# pca10040_sheet5_power_supply.net
KiCad netlist of a schematic drawn in Altium Designer
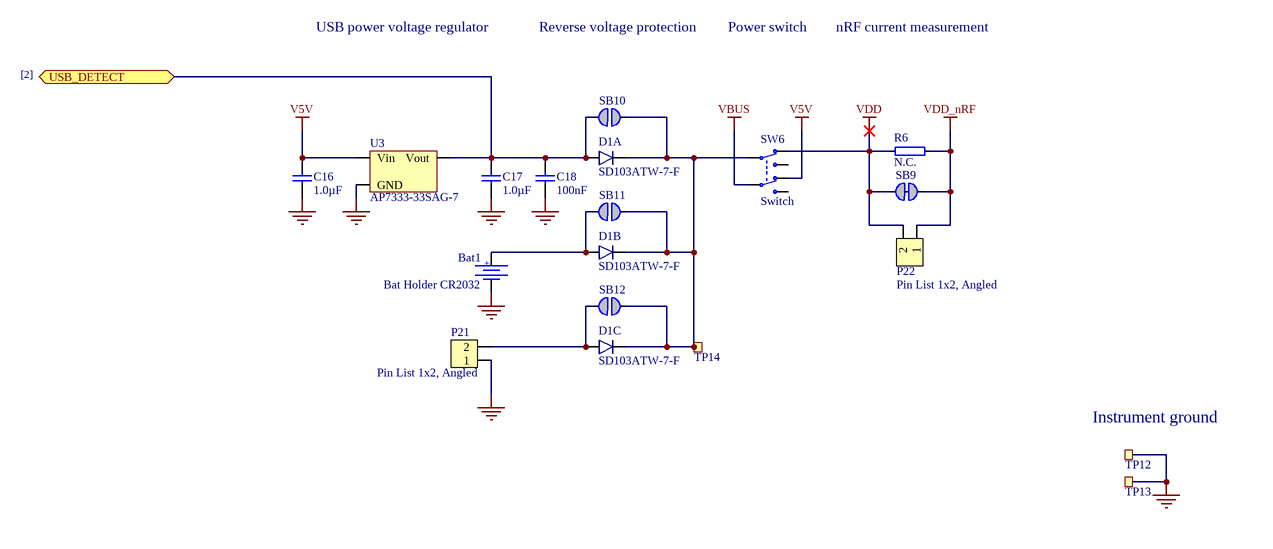
[diagram p0: pca10040_sheet5_power_supply.SchDoc]

(export (version "E")
  (design (tool "Eeschema 10.0.6"))
  (components
    (comp (ref "Bat1")
      (value "Bat Holder CR2032")
      (footprint "CR2032_HOLDER_SMD")
      (description "Bat Holder CR2032 SMD")
      (fields
        (field (name "MANUFACTURER") "Keystone")
        (field (name "MANUFACTURER PART NUMBER") "3002")
        (field (name "PUBLISHER") "Nordic Semiconductor")
      )
      (libsource (lib "Nordic Passive DB") (part "Battery"))
    )
    (comp (ref "C16")
      (value "1.0µF")
      (footprint "CAPC1608X06L")
      (description "Capacitor, X7R, ±10%")
      (fields (field (name "PART NUMBER") "C0603-1µ0") (field (name "PUBLISHER") "Nordic Semiconductor"))
      (libsource (lib "Nordic Passive DB") (part "CAP"))
    )
    (comp (ref "C17")
      (value "1.0µF")
      (footprint "CAPC1608X06L")
      (description "Capacitor, X7R, ±10%")
      (fields (field (name "PART NUMBER") "C0603-1µ0") (field (name "PUBLISHER") "Nordic Semiconductor"))
      (libsource (lib "Nordic Passive DB") (part "CAP"))
    )
    (comp (ref "C18")
      (value "100nF")
      (footprint "CAPC1005X04L")
      (description "Capacitor, X7R, ±10%")
      (fields (field (name "PART NUMBER") "C0402-100n") (field (name "PUBLISHER") "Nordic Semiconductor"))
      (libsource (lib "Nordic Passive DB") (part "CAP"))
    )
    (comp (ref "D1")
      (value "SD103ATW-7-F")
      (footprint "SOT-363")
      (description "Surface Mount Schottky Barrier Diode Array")
      (fields
        (field (name "MANUFACTURER") "Diodes Incorporated")
        (field (name "2ND SOURCE PART NUMBER") "177-3507")
        (field (name "PUBLISHER") "Nordic Semiconductor")
      )
      (libsource (lib "Nordic Discrete DB") (part "D{colon}DIODE_3_IND"))
    )
    (comp (ref "P21")
      (value "Pin List 1x2, Angled")
      (footprint "LIST_ANG_1x2-SMD-2.54MM")
      (description "Pin List 1x2, 2.54mm (100mil), Right Angled, SMD")
      (fields
        (field (name "PART NUMBER") "Pin List Ang 1x2 SMD, 2.54mm")
        (field (name "MANUFACTURER") "Cabcon")
        (field (name "PUBLISHER") "Nordic Semiconductor")
      )
      (libsource (lib "") (part "CONN-2_1"))
    )
    (comp (ref "P22")
      (value "Pin List 1x2, Angled")
      (footprint "LIST_ANG_1x2-SMD-2.54MM")
      (description "Pin List 1x2, 2.54mm (100mil), Right Angled, SMD")
      (fields
        (field (name "PART NUMBER") "Pin List Ang 1x2 SMD, 2.54mm")
        (field (name "MANUFACTURER") "Cabcon")
        (field (name "PUBLISHER") "Nordic Semiconductor")
      )
      (libsource (lib "Nordic Passive DB") (part "CONN-2"))
    )
    (comp (ref "R6")
      (value "N.C.")
      (footprint "RESC1005X04L")
      (description "Not mounted")
      (fields (field (name "PART NUMBER") "R0402-N.C.") (field (name "PUBLISHER") "Nordic Semiconductor"))
      (libsource (lib "Nordic Passive DB") (part "RES_1"))
    )
    (comp (ref "SB9")
      (value "Solderbridge")
      (footprint "Solderbridge_Shorted")
      (description "Shorted Solderbridge")
      (fields
        (field (name "PART NUMBER") "Solderbridge Shorted")
        (field (name "PUBLISHER") "Nordic Semiconductor")
      )
      (libsource (lib "Nordic Passive DB") (part "SOLDERBRIDGE_SHORTED"))
    )
    (comp (ref "SB10")
      (value "Solderbridge")
      (footprint "Solderbridge")
      (fields (field (name "PUBLISHER") "Nordic Semiconductor"))
      (libsource (lib "Nordic Passive DB") (part "SOLDERBRIDGE"))
    )
    (comp (ref "SB11")
      (value "Solderbridge")
      (footprint "Solderbridge")
      (fields (field (name "PUBLISHER") "Nordic Semiconductor"))
      (libsource (lib "Nordic Passive DB") (part "SOLDERBRIDGE"))
    )
    (comp (ref "SB12")
      (value "Solderbridge")
      (footprint "Solderbridge")
      (fields (field (name "PUBLISHER") "Nordic Semiconductor"))
      (libsource (lib "Nordic Passive DB") (part "SOLDERBRIDGE"))
    )
    (comp (ref "SW6")
      (value "Switch")
      (footprint "JS202011SCQN")
      (description "SMD slide Switch (ON-ON)")
      (fields
        (field (name "PART NUMBER") "JS202011SCQN")
        (field (name "MANUFACTURER") "C&K Components")
        (field (name "PUBLISHER") "Nordic Semiconductor")
      )
      (libsource (lib "Nordic Discrete DB") (part "SW-DPDT"))
    )
    (comp (ref "TP12")
      (value "TP")
      (footprint "TESTPAD-TH")
      (description "Testpoint, through hole")
      (fields (field (name "PART NUMBER") "Testpoint TH") (field (name "PUBLISHER") "Nordic Semiconductor"))
      (libsource (lib "") (part "TESTPAD_1"))
    )
    (comp (ref "TP13")
      (value "TP")
      (footprint "TESTPAD-TH")
      (description "Testpoint, through hole")
      (fields (field (name "PART NUMBER") "Testpoint TH") (field (name "PUBLISHER") "Nordic Semiconductor"))
      (libsource (lib "") (part "TESTPAD_1"))
    )
    (comp (ref "TP14")
      (value "Ø1.0mm,SMD")
      (footprint "TP_SMD_Ø1.0mm")
      (description "1.0mm circular SMD testpad")
      (fields
        (field (name "PART NUMBER") "TP_SMD_Ø1.0MM")
        (field (name "MANUFACTURER") "Nordic Semiconductor")
        (field (name "PUBLISHER") "Nordic Semiconductor")
      )
      (libsource (lib "Nordic Passive DB") (part "TESTPAD"))
    )
    (comp (ref "U3")
      (value "AP7333-33SAG-7")
      (footprint "SOT-23A")
      (description "300mA, Low Quiescent Current, Fast Transient Low Dropout Linear Regulator")
      (fields
        (field (name "MANUFACTURER") "Diodes Incorporated")
        (field (name "PUBLISHER") "Nordic Semiconductor")
      )
      (libsource (lib "Nordic Active DB") (part "AP7333-XXSAG"))
    )
  )
  (nets
    (net (code "1") (name "/USB_DETECT") (class "Default")
      (node (ref "C17") (pin "2") (pinfunction "2_2") (pintype "passive"))
      (node (ref "C18") (pin "2") (pinfunction "2_2") (pintype "passive"))
      (node (ref "D1") (pin "6") (pinfunction "A1_6") (pintype "passive"))
      (node (ref "SB10") (pin "2") (pinfunction "1_2") (pintype "passive"))
      (node (ref "U3") (pin "2") (pinfunction "Vout_2") (pintype "passive"))
    )
    (net (code "2") (name "GND") (class "Default")
      (node (ref "Bat1") (pin "2") (pintype "passive"))
      (node (ref "C16") (pin "1") (pinfunction "1_1") (pintype "passive"))
      (node (ref "C17") (pin "1") (pinfunction "1_1") (pintype "passive"))
      (node (ref "C18") (pin "1") (pinfunction "1_1") (pintype "passive"))
      (node (ref "P21") (pin "1") (pinfunction "1_1") (pintype "passive"))
      (node (ref "TP12") (pin "1") (pinfunction "1_1") (pintype "passive"))
      (node (ref "TP13") (pin "1") (pinfunction "1_1") (pintype "passive"))
      (node (ref "U3") (pin "3") (pinfunction "GND_3") (pintype "passive"))
    )
    (net (code "3") (name "Net-(D1A-C1)") (class "Default")
      (node (ref "D1") (pin "1") (pinfunction "C1_1") (pintype "passive"))
      (node (ref "D1") (pin "2") (pinfunction "C2_2") (pintype "passive"))
      (node (ref "D1") (pin "3") (pinfunction "C3_3") (pintype "passive"))
      (node (ref "SB10") (pin "1") (pinfunction "0_1") (pintype "passive"))
      (node (ref "SB11") (pin "1") (pinfunction "0_1") (pintype "passive"))
      (node (ref "SB12") (pin "1") (pinfunction "0_1") (pintype "passive"))
      (node (ref "SW6") (pin "2") (pinfunction "COM-1_2") (pintype "passive"))
      (node (ref "TP14") (pin "1") (pinfunction "1_1") (pintype "passive"))
    )
    (net (code "4") (name "Net-(D1B-A2)") (class "Default")
      (node (ref "Bat1") (pin "1") (pintype "passive"))
      (node (ref "D1") (pin "5") (pinfunction "A2_5") (pintype "passive"))
      (node (ref "SB11") (pin "2") (pinfunction "1_2") (pintype "passive"))
    )
    (net (code "5") (name "Net-(D1C-A3)") (class "Default")
      (node (ref "D1") (pin "4") (pinfunction "A3_4") (pintype "passive"))
      (node (ref "P21") (pin "2") (pinfunction "2_2") (pintype "passive"))
      (node (ref "SB12") (pin "2") (pinfunction "1_2") (pintype "passive"))
    )
    (net (code "6") (name "V5V") (class "Default")
      (node (ref "C16") (pin "2") (pinfunction "2_2") (pintype "passive"))
      (node (ref "SW6") (pin "6") (pinfunction "N.C-2_6") (pintype "passive"))
      (node (ref "U3") (pin "1") (pinfunction "Vin_1") (pintype "passive"))
    )
    (net (code "7") (name "VBUS") (class "Default")
      (node (ref "SW6") (pin "5") (pinfunction "COM-2_5") (pintype "passive"))
    )
    (net (code "8") (name "VDD") (class "Default")
      (node (ref "P22") (pin "2") (pinfunction "2_2") (pintype "passive"))
      (node (ref "R6") (pin "1") (pinfunction "1_1") (pintype "passive"))
      (node (ref "SB9") (pin "2") (pinfunction "1_2") (pintype "passive"))
      (node (ref "SW6") (pin "3") (pinfunction "N.C-1_3") (pintype "passive"))
    )
    (net (code "9") (name "VDD_nRF") (class "Default")
      (node (ref "P22") (pin "1") (pinfunction "1_1") (pintype "passive"))
      (node (ref "R6") (pin "2") (pinfunction "2_2") (pintype "passive"))
      (node (ref "SB9") (pin "1") (pinfunction "0_1") (pintype "passive"))
    )
    (net (code "10") (name "unconnected-(SW6-N.O-1-Pad1)") (class "Default")
      (node (ref "SW6") (pin "1") (pinfunction "N.O-1_1") (pintype "passive"))
    )
    (net (code "11") (name "unconnected-(SW6-N.O-2-Pad4)") (class "Default")
      (node (ref "SW6") (pin "4") (pinfunction "N.O-2_4") (pintype "passive"))
    )
  )
)
